# MICROCONTROLLER.net
KiCad netlist of a schematic drawn in Altium Designer
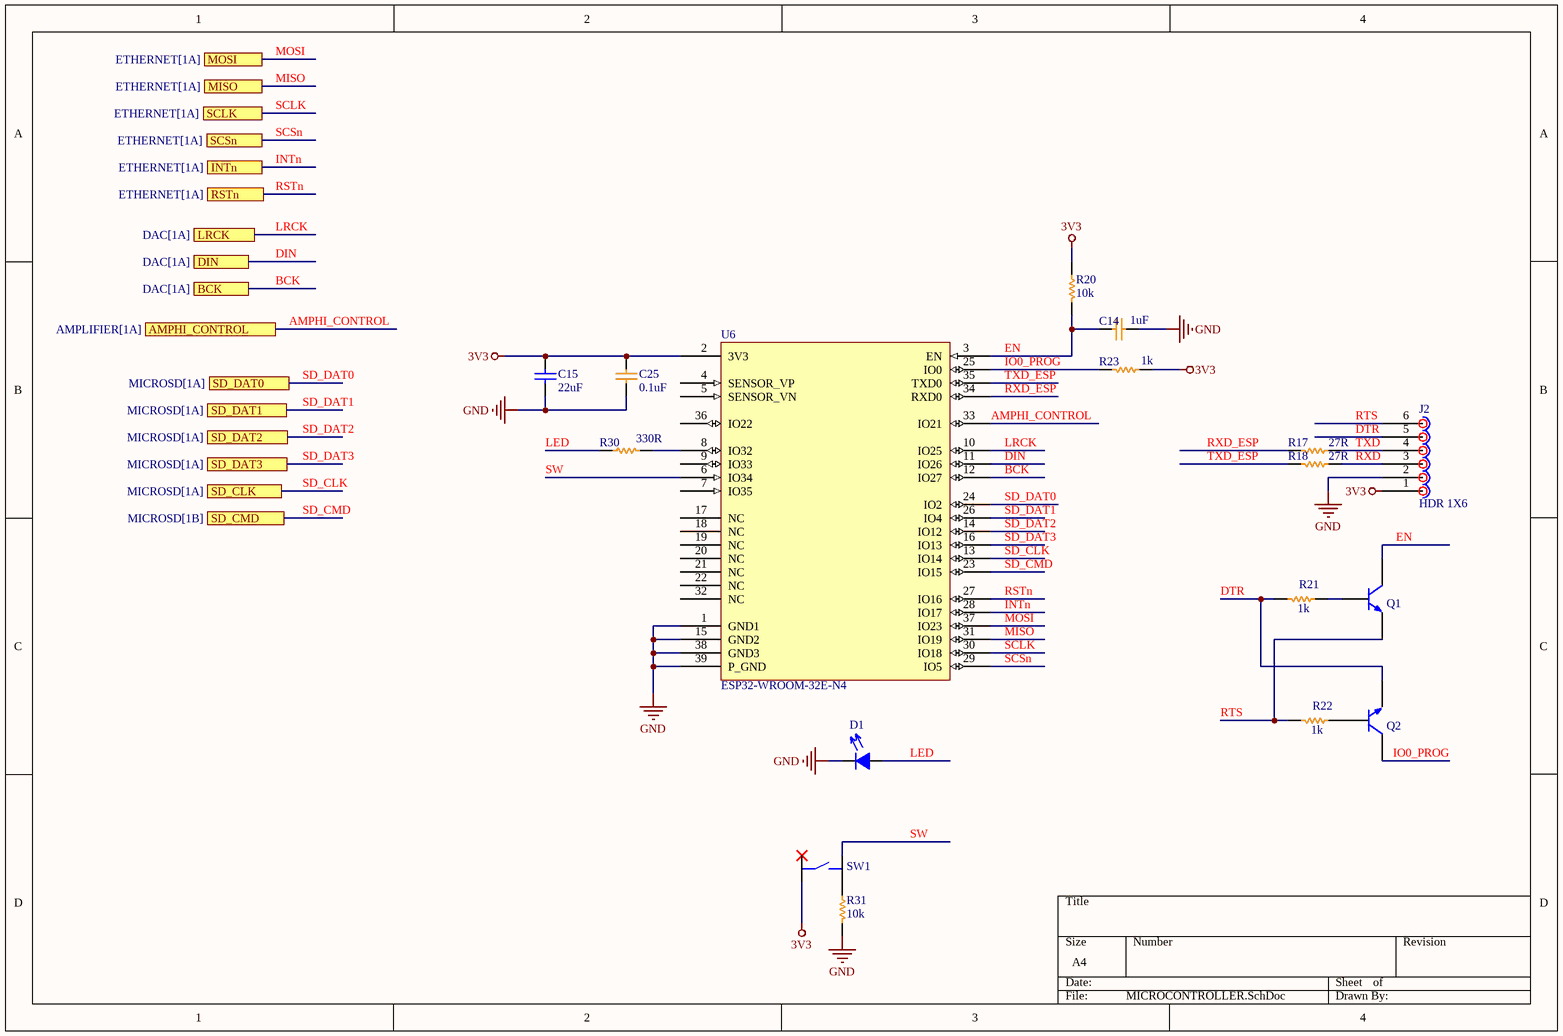
[diagram p0: MICROCONTROLLER.SchDoc]

(export (version "E")
  (design (tool "Eeschema 10.0.6"))
  (components
    (comp (ref "C14")
      (value "1uF")
      (footprint "CAP-0603")
      (description "CAP CER 1UF 10V X7R 0603")
      (libsource (lib "Schlib1") (part "CAP-0603"))
    )
    (comp (ref "C15")
      (value "22uF")
      (footprint "CAP-0805")
      (description "CAP CER 22UF 10V X5R 0805")
      (libsource (lib "Schlib1") (part "CAP-0805"))
    )
    (comp (ref "C25")
      (value "0.1uF")
      (footprint "CAP-0603")
      (description "CAP CER 0.1UF 10V X7R 0603")
      (libsource (lib "Schlib1") (part "CAP-0603"))
    )
    (comp (ref "D1")
      (value "LTST-C170GKT")
      (footprint "LED-0805")
      (description "LED GREEN CLEAR SMD")
      (libsource (lib "schematic") (part "LTST-C170GKT"))
    )
    (comp (ref "J2") (value "HDR 1X6") (footprint "HDR 1X6") (libsource (lib "Schlib1") (part "HDR 1X6")))
    (comp (ref "Q1")
      (value "S8050")
      (footprint "SOT-23")
      (description "TRANS NPN 25V 0.5A SOT-23")
      (libsource (lib "schematic") (part "S8050"))
    )
    (comp (ref "Q2")
      (value "S8050")
      (footprint "SOT-23")
      (description "TRANS NPN 25V 0.5A SOT-23")
      (libsource (lib "schematic") (part "S8050"))
    )
    (comp (ref "R17")
      (value "27R")
      (footprint "RES-0603")
      (description "RES SMD 27 OHM 1% 1/10W 0603")
      (libsource (lib "Schlib1") (part "RES-0603"))
    )
    (comp (ref "R18")
      (value "27R")
      (footprint "RES-0603")
      (description "RES SMD 27 OHM 1% 1/10W 0603")
      (libsource (lib "Schlib1") (part "RES-0603"))
    )
    (comp (ref "R20")
      (value "10k")
      (footprint "RES-0603")
      (description "RES SMD 10K OHM 1% 1/10W 0603")
      (libsource (lib "Schlib1") (part "RES-0603"))
    )
    (comp (ref "R21")
      (value "1k")
      (footprint "RES-0603")
      (description "RES SMD 1K OHM 1% 1/10W 0603")
      (libsource (lib "Schlib1") (part "RES-0603"))
    )
    (comp (ref "R22")
      (value "1k")
      (footprint "RES-0603")
      (description "RES SMD 1K OHM 1% 1/10W 0603")
      (libsource (lib "Schlib1") (part "RES-0603"))
    )
    (comp (ref "R23")
      (value "1k")
      (footprint "RES-0603")
      (description "RES SMD 1K OHM 1% 1/10W 0603")
      (libsource (lib "Schlib1") (part "RES-0603"))
    )
    (comp (ref "R30")
      (value "330R")
      (footprint "RES-0603")
      (description "RES SMD 330 OHM 5% 1/10W 0603")
      (libsource (lib "Schlib1") (part "RES-0603"))
    )
    (comp (ref "R31")
      (value "10k")
      (footprint "RES-0603")
      (description "RES SMD 10K OHM 1% 1/10W 0603")
      (libsource (lib "Schlib1") (part "RES-0603"))
    )
    (comp (ref "SW1")
      (value "PTS645SK43SMTR92 LFS")
      (footprint "SW-SMD-6x6")
      (description "G TYPE SMT SWITCH TACTILE SPST-NO 0.05A 12V")
      (libsource (lib "schematic") (part "PTS645SK43SMTR92 LFS"))
    )
    (comp (ref "U6")
      (value "ESP32-WROOM-32E-N4")
      (footprint "ESP32-WROOM-32E-N4")
      (description "RF TXRX MOD BT WIFI TH SMD")
      (libsource (lib "schematic") (part "ESP32-WROOM-32E-N4"))
    )
  )
  (nets
    (net (code "1") (name "/AMPHI_CONTROL") (class "Default")
      (node (ref "U6") (pin "33") (pinfunction "IO21_33") (pintype "bidirectional"))
    )
    (net (code "2") (name "/BCK") (class "Default")
      (node (ref "U6") (pin "12") (pinfunction "IO27_12") (pintype "bidirectional"))
    )
    (net (code "3") (name "/DIN") (class "Default")
      (node (ref "U6") (pin "11") (pinfunction "IO26_11") (pintype "bidirectional"))
    )
    (net (code "4") (name "/DTR") (class "Default")
      (node (ref "J2") (pin "5") (pinfunction "5_5") (pintype "passive"))
      (node (ref "Q2") (pin "2") (pinfunction "2_2") (pintype "passive"))
      (node (ref "R21") (pin "1") (pinfunction "1_1") (pintype "passive"))
    )
    (net (code "5") (name "/EN") (class "Default")
      (node (ref "C14") (pin "2") (pinfunction "2_2") (pintype "passive"))
      (node (ref "Q1") (pin "3") (pinfunction "3_3") (pintype "passive"))
      (node (ref "R20") (pin "1") (pinfunction "1_1") (pintype "passive"))
      (node (ref "U6") (pin "3") (pinfunction "EN_3") (pintype "input"))
    )
    (net (code "6") (name "/INTn") (class "Default")
      (node (ref "U6") (pin "28") (pinfunction "IO17_28") (pintype "bidirectional"))
    )
    (net (code "7") (name "/IO0_PROG") (class "Default")
      (node (ref "Q2") (pin "3") (pinfunction "3_3") (pintype "passive"))
      (node (ref "R23") (pin "1") (pinfunction "1_1") (pintype "passive"))
      (node (ref "U6") (pin "25") (pinfunction "IO0_25") (pintype "bidirectional"))
    )
    (net (code "8") (name "/LED") (class "Default")
      (node (ref "D1") (pin "1") (pinfunction "1_1") (pintype "passive"))
      (node (ref "R30") (pin "2") (pinfunction "2_2") (pintype "passive"))
    )
    (net (code "9") (name "/LRCK") (class "Default")
      (node (ref "U6") (pin "10") (pinfunction "IO25_10") (pintype "bidirectional"))
    )
    (net (code "10") (name "/MISO") (class "Default")
      (node (ref "U6") (pin "31") (pinfunction "IO19_31") (pintype "bidirectional"))
    )
    (net (code "11") (name "/MOSI") (class "Default")
      (node (ref "U6") (pin "37") (pinfunction "IO23_37") (pintype "bidirectional"))
    )
    (net (code "12") (name "/RSTn") (class "Default")
      (node (ref "U6") (pin "27") (pinfunction "IO16_27") (pintype "bidirectional"))
    )
    (net (code "13") (name "/RTS") (class "Default")
      (node (ref "J2") (pin "6") (pintype "passive"))
      (node (ref "Q1") (pin "2") (pinfunction "2_2") (pintype "passive"))
      (node (ref "R22") (pin "1") (pinfunction "1_1") (pintype "passive"))
    )
    (net (code "14") (name "/RXD") (class "Default")
      (node (ref "J2") (pin "3") (pintype "passive"))
      (node (ref "R18") (pin "2") (pinfunction "2_2") (pintype "passive"))
    )
    (net (code "15") (name "/RXD_ESP") (class "Default")
      (node (ref "R17") (pin "1") (pinfunction "1_1") (pintype "passive"))
      (node (ref "U6") (pin "34") (pinfunction "RXD0_34") (pintype "bidirectional"))
    )
    (net (code "16") (name "/SCLK") (class "Default")
      (node (ref "U6") (pin "30") (pinfunction "IO18_30") (pintype "bidirectional"))
    )
    (net (code "17") (name "/SCSn") (class "Default")
      (node (ref "U6") (pin "29") (pinfunction "IO5_29") (pintype "bidirectional"))
    )
    (net (code "18") (name "/SD_CLK") (class "Default")
      (node (ref "U6") (pin "13") (pinfunction "IO14_13") (pintype "bidirectional"))
    )
    (net (code "19") (name "/SD_CMD") (class "Default")
      (node (ref "U6") (pin "23") (pinfunction "IO15_23") (pintype "bidirectional"))
    )
    (net (code "20") (name "/SD_DAT0") (class "Default")
      (node (ref "U6") (pin "24") (pinfunction "IO2_24") (pintype "bidirectional"))
    )
    (net (code "21") (name "/SD_DAT1") (class "Default")
      (node (ref "U6") (pin "26") (pinfunction "IO4_26") (pintype "bidirectional"))
    )
    (net (code "22") (name "/SD_DAT2") (class "Default")
      (node (ref "U6") (pin "14") (pinfunction "IO12_14") (pintype "bidirectional"))
    )
    (net (code "23") (name "/SD_DAT3") (class "Default")
      (node (ref "U6") (pin "16") (pinfunction "IO13_16") (pintype "bidirectional"))
    )
    (net (code "24") (name "/SW") (class "Default")
      (node (ref "SW1") (pin "1") (pinfunction "1_1") (pintype "passive"))
      (node (ref "U6") (pin "6") (pinfunction "IO34_6") (pintype "input"))
    )
    (net (code "25") (name "/TXD") (class "Default")
      (node (ref "J2") (pin "4") (pintype "passive"))
      (node (ref "R17") (pin "2") (pinfunction "2_2") (pintype "passive"))
    )
    (net (code "26") (name "/TXD_ESP") (class "Default")
      (node (ref "R18") (pin "1") (pinfunction "1_1") (pintype "passive"))
      (node (ref "U6") (pin "35") (pinfunction "TXD0_35") (pintype "bidirectional"))
    )
    (net (code "27") (name "3V3") (class "Default")
      (node (ref "C15") (pin "2") (pinfunction "2_2") (pintype "passive"))
      (node (ref "C25") (pin "2") (pinfunction "2_2") (pintype "passive"))
      (node (ref "J2") (pin "1") (pintype "passive"))
      (node (ref "R20") (pin "2") (pinfunction "2_2") (pintype "passive"))
      (node (ref "R23") (pin "2") (pinfunction "2_2") (pintype "passive"))
      (node (ref "SW1") (pin "4") (pinfunction "4_4") (pintype "passive"))
      (node (ref "U6") (pin "2") (pinfunction "3V3_2") (pintype "power_in"))
    )
    (net (code "28") (name "GND") (class "Default")
      (node (ref "C14") (pin "1") (pinfunction "1_1") (pintype "passive"))
      (node (ref "C15") (pin "1") (pinfunction "1_1") (pintype "passive"))
      (node (ref "C25") (pin "1") (pinfunction "1_1") (pintype "passive"))
      (node (ref "D1") (pin "2") (pinfunction "2_2") (pintype "passive"))
      (node (ref "J2") (pin "2") (pintype "passive"))
      (node (ref "R31") (pin "1") (pinfunction "1_1") (pintype "passive"))
      (node (ref "U6") (pin "1") (pinfunction "GND1_1") (pintype "power_in"))
      (node (ref "U6") (pin "15") (pinfunction "GND2_15") (pintype "power_in"))
      (node (ref "U6") (pin "38") (pinfunction "GND3_38") (pintype "power_in"))
      (node (ref "U6") (pin "39") (pinfunction "P_GND_39") (pintype "power_in"))
    )
    (net (code "29") (name "Net-(Q1-Pad1)") (class "Default")
      (node (ref "Q1") (pin "1") (pinfunction "1_1") (pintype "passive"))
      (node (ref "R21") (pin "2") (pinfunction "2_2") (pintype "passive"))
    )
    (net (code "30") (name "Net-(Q2-Pad1)") (class "Default")
      (node (ref "Q2") (pin "1") (pinfunction "1_1") (pintype "passive"))
      (node (ref "R22") (pin "2") (pinfunction "2_2") (pintype "passive"))
    )
    (net (code "31") (name "Net-(R31-Pad2)") (class "Default")
      (node (ref "R31") (pin "2") (pinfunction "2_2") (pintype "passive"))
      (node (ref "SW1") (pin "2") (pinfunction "2_2") (pintype "passive"))
    )
    (net (code "32") (name "Net-(U6-IO32)") (class "Default")
      (node (ref "R30") (pin "1") (pinfunction "1_1") (pintype "passive"))
      (node (ref "U6") (pin "8") (pinfunction "IO32_8") (pintype "bidirectional"))
    )
    (net (code "33") (name "unconnected-(SW1-Pad3)") (class "Default")
      (node (ref "SW1") (pin "3") (pinfunction "3_3") (pintype "passive+no_connect"))
    )
    (net (code "34") (name "unconnected-(U6-IO22-Pad36)") (class "Default")
      (node (ref "U6") (pin "36") (pinfunction "IO22_36") (pintype "bidirectional"))
    )
    (net (code "35") (name "unconnected-(U6-IO33-Pad9)") (class "Default")
      (node (ref "U6") (pin "9") (pinfunction "IO33_9") (pintype "bidirectional"))
    )
    (net (code "36") (name "unconnected-(U6-IO35-Pad7)") (class "Default")
      (node (ref "U6") (pin "7") (pinfunction "IO35_7") (pintype "input"))
    )
    (net (code "37") (name "unconnected-(U6-NC-Pad17)") (class "Default")
      (node (ref "U6") (pin "17") (pinfunction "NC_17") (pintype "passive"))
    )
    (net (code "38") (name "unconnected-(U6-NC-Pad18)") (class "Default")
      (node (ref "U6") (pin "18") (pinfunction "NC_18") (pintype "passive"))
    )
    (net (code "39") (name "unconnected-(U6-NC-Pad19)") (class "Default")
      (node (ref "U6") (pin "19") (pinfunction "NC_19") (pintype "passive"))
    )
    (net (code "40") (name "unconnected-(U6-NC-Pad20)") (class "Default")
      (node (ref "U6") (pin "20") (pinfunction "NC_20") (pintype "passive"))
    )
    (net (code "41") (name "unconnected-(U6-NC-Pad21)") (class "Default")
      (node (ref "U6") (pin "21") (pinfunction "NC_21") (pintype "passive"))
    )
    (net (code "42") (name "unconnected-(U6-NC-Pad22)") (class "Default")
      (node (ref "U6") (pin "22") (pinfunction "NC_22") (pintype "passive"))
    )
    (net (code "43") (name "unconnected-(U6-NC-Pad32)") (class "Default")
      (node (ref "U6") (pin "32") (pinfunction "NC_32") (pintype "passive"))
    )
    (net (code "44") (name "unconnected-(U6-SENSOR_VN-Pad5)") (class "Default")
      (node (ref "U6") (pin "5") (pinfunction "SENSOR_VN_5") (pintype "input"))
    )
    (net (code "45") (name "unconnected-(U6-SENSOR_VP-Pad4)") (class "Default")
      (node (ref "U6") (pin "4") (pinfunction "SENSOR_VP_4") (pintype "input"))
    )
  )
)
